# boiler_schematic.net
KiCad netlist of a schematic drawn in EAGLE
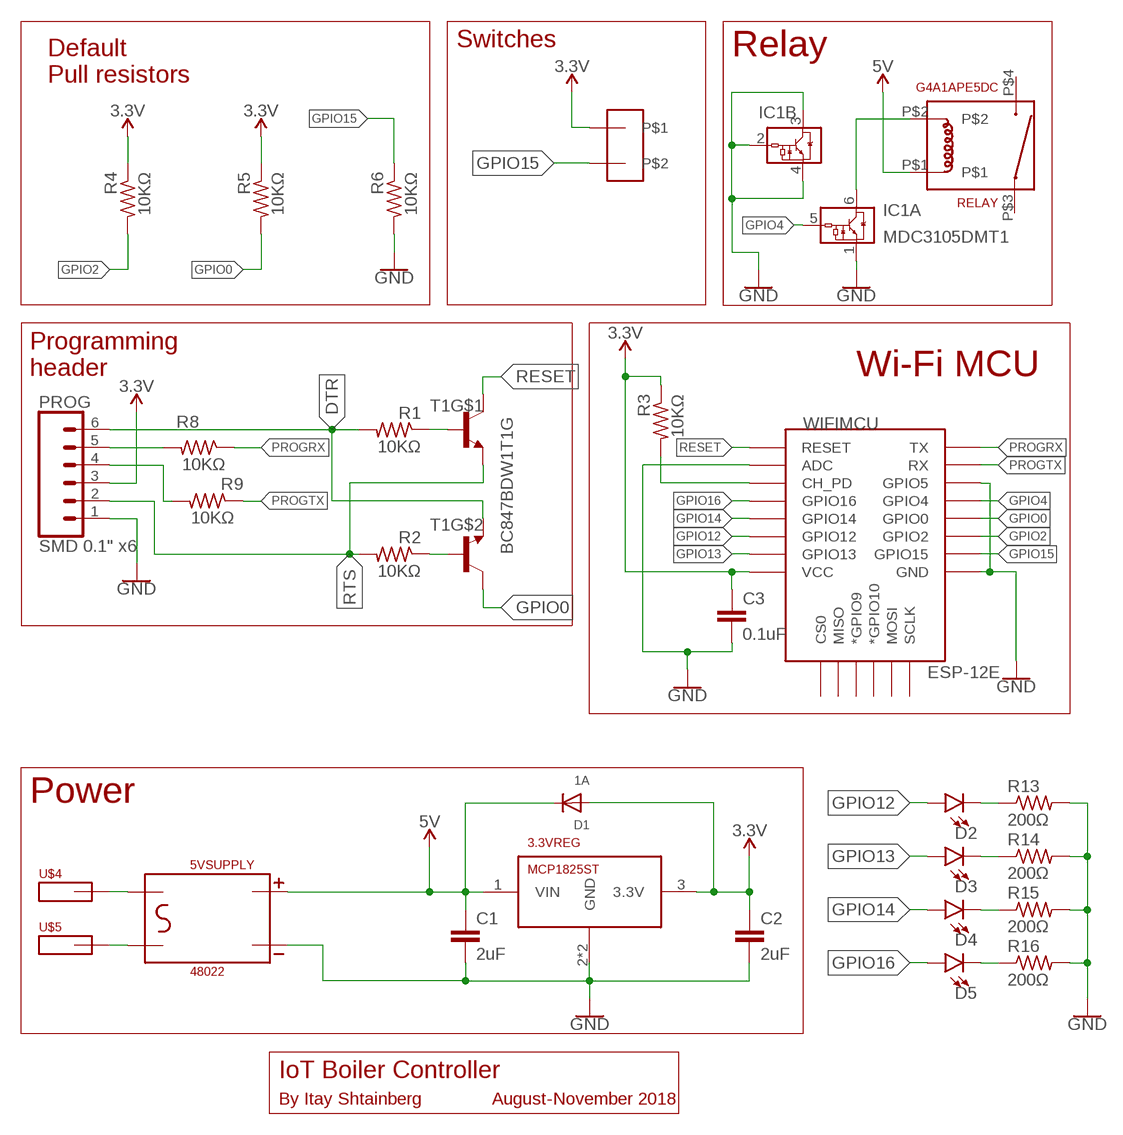
[diagram p0: schematic, sheet 1]

(export (version "E")
  (design (tool "Eeschema 10.0.6"))
  (components
    (comp (ref "3.3VREG")
      (value "MCP1825ST")
      (footprint "eagle-import:SOT223")
      (libsource (lib "eagle-import") (part "MCP1825ST-3302E/DB"))
    )
    (comp (ref "5VSUPPLY")
      (value "48022")
      (footprint "eagle-import:48022")
      (libsource (lib "eagle-import") (part "48022"))
    )
    (comp (ref "C1")
      (value "2uF")
      (footprint "eagle-import:C0805")
      (libsource (lib "eagle-import") (part "C"))
    )
    (comp (ref "C2")
      (value "2uF")
      (footprint "eagle-import:C0805")
      (libsource (lib "eagle-import") (part "C"))
    )
    (comp (ref "C3")
      (value "0.1uF")
      (footprint "eagle-import:C0805")
      (libsource (lib "eagle-import") (part "C"))
    )
    (comp (ref "D1")
      (value "1A")
      (footprint "eagle-import:SOD-123")
      (libsource (lib "eagle-import") (part "DIODESOD-123"))
    )
    (comp (ref "D2")
      (value "LED1206")
      (footprint "eagle-import:LED-1206")
      (libsource (lib "eagle-import") (part "LED1206"))
    )
    (comp (ref "D3")
      (value "LED1206")
      (footprint "eagle-import:LED-1206")
      (libsource (lib "eagle-import") (part "LED1206"))
    )
    (comp (ref "D4")
      (value "LED1206")
      (footprint "eagle-import:LED-1206")
      (libsource (lib "eagle-import") (part "LED1206"))
    )
    (comp (ref "D5")
      (value "LED1206")
      (footprint "eagle-import:LED-1206")
      (libsource (lib "eagle-import") (part "LED1206"))
    )
    (comp (ref "IC1")
      (value "MDC3105DMT1")
      (footprint "eagle-import:SC-74")
      (fields (field (name "MPN") "MDC3105DMT1G"))
      (libsource (lib "eagle-import") (part "MDC3105DMT1"))
    )
    (comp (ref "PROG")
      (value "SMD 0.1\" x6")
      (footprint "eagle-import:1X06-SMD-FEMALE")
      (libsource (lib "eagle-import") (part "CONN_06SMD-FEMALE-V2"))
    )
    (comp (ref "R1")
      (value "10KΩ")
      (footprint "eagle-import:R0805")
      (libsource (lib "eagle-import") (part "rcl_334_R-US_R0805"))
    )
    (comp (ref "R2")
      (value "10KΩ")
      (footprint "eagle-import:R0805")
      (libsource (lib "eagle-import") (part "rcl_334_R-US_R0805"))
    )
    (comp (ref "R3")
      (value "10KΩ")
      (footprint "eagle-import:R0805")
      (libsource (lib "eagle-import") (part "rcl_334_R-US_R0805"))
    )
    (comp (ref "R4")
      (value "10KΩ")
      (footprint "eagle-import:R0805")
      (libsource (lib "eagle-import") (part "rcl_334_R-US_R0805"))
    )
    (comp (ref "R5")
      (value "10KΩ")
      (footprint "eagle-import:R0805")
      (libsource (lib "eagle-import") (part "rcl_334_R-US_R0805"))
    )
    (comp (ref "R6")
      (value "10KΩ")
      (footprint "eagle-import:R0805")
      (libsource (lib "eagle-import") (part "rcl_334_R-US_R0805"))
    )
    (comp (ref "R8")
      (value "10KΩ")
      (footprint "eagle-import:R0805")
      (libsource (lib "eagle-import") (part "rcl_334_R-US_R0805"))
    )
    (comp (ref "R9")
      (value "10KΩ")
      (footprint "eagle-import:R0805")
      (libsource (lib "eagle-import") (part "rcl_334_R-US_R0805"))
    )
    (comp (ref "R13")
      (value "200Ω")
      (footprint "eagle-import:R1206")
      (libsource (lib "eagle-import") (part "R-US_R1206"))
    )
    (comp (ref "R14")
      (value "200Ω")
      (footprint "eagle-import:R1206")
      (libsource (lib "eagle-import") (part "R-US_R1206"))
    )
    (comp (ref "R15")
      (value "200Ω")
      (footprint "eagle-import:R1206")
      (libsource (lib "eagle-import") (part "R-US_R1206"))
    )
    (comp (ref "R16")
      (value "200Ω")
      (footprint "eagle-import:R1206")
      (libsource (lib "eagle-import") (part "R-US_R1206"))
    )
    (comp (ref "RELAY")
      (value "G4A1APE5DC")
      (footprint "eagle-import:G4A-1A-E")
      (libsource (lib "eagle-import") (part "G4A-1A-E"))
    )
    (comp (ref "T1")
      (value "BC847BDW1T1G")
      (footprint "eagle-import:SC70-6")
      (libsource (lib "eagle-import") (part "BC847BDW1T1G"))
    )
    (comp (ref "U$1")
      (value "JST2PIN")
      (footprint "eagle-import:JST2PIN")
      (libsource (lib "eagle-import") (part "JST2PIN"))
    )
    (comp (ref "U$4")
      (value "QUICKDISCONNECT2")
      (footprint "eagle-import:QUICKDISCONNECT2")
      (libsource (lib "eagle-import") (part "QUICKDISCONNECT2"))
    )
    (comp (ref "U$5")
      (value "QUICKDISCONNECT2")
      (footprint "eagle-import:QUICKDISCONNECT2")
      (libsource (lib "eagle-import") (part "QUICKDISCONNECT2"))
    )
    (comp (ref "WIFIMCU")
      (value "ESP-12E")
      (footprint "eagle-import:ESP12E-SMD")
      (libsource (lib "eagle-import") (part "ESP12ESMD"))
    )
  )
  (nets
    (net (code "1") (name "3.3V") (class "Default")
      (node (ref "3.3VREG") (pin "3") (pinfunction "3.3V_3") (pintype "power_in"))
      (node (ref "C2") (pin "1") (pinfunction "1_1") (pintype "passive"))
      (node (ref "C3") (pin "1") (pinfunction "1_1") (pintype "passive"))
      (node (ref "D1") (pin "A") (pinfunction "A_A") (pintype "passive"))
      (node (ref "PROG") (pin "3") (pinfunction "3_3") (pintype "passive"))
      (node (ref "R3") (pin "1") (pinfunction "1_1") (pintype "passive"))
      (node (ref "R4") (pin "1") (pinfunction "1_1") (pintype "passive"))
      (node (ref "R5") (pin "1") (pinfunction "1_1") (pintype "passive"))
      (node (ref "U$1") (pin "P$1") (pinfunction "P$1_P$1") (pintype "bidirectional"))
      (node (ref "WIFIMCU") (pin "VCC") (pinfunction "VCC_VCC") (pintype "bidirectional"))
    )
    (net (code "2") (name "5V") (class "Default")
      (node (ref "3.3VREG") (pin "1") (pinfunction "VIN_1") (pintype "power_in"))
      (node (ref "5VSUPPLY") (pin "+5V") (pinfunction "+5V_+5V") (pintype "bidirectional"))
      (node (ref "C1") (pin "1") (pinfunction "1_1") (pintype "passive"))
      (node (ref "D1") (pin "C") (pinfunction "C_C") (pintype "passive"))
      (node (ref "RELAY") (pin "P$1") (pinfunction "P$1_P$1") (pintype "bidirectional"))
    )
    (net (code "3") (name "DTR") (class "Default")
      (node (ref "PROG") (pin "6") (pinfunction "6_6") (pintype "passive"))
      (node (ref "R1") (pin "2") (pinfunction "2_2") (pintype "passive"))
      (node (ref "T1") (pin "4") (pinfunction "E_4") (pintype "passive"))
    )
    (net (code "4") (name "GND") (class "Default")
      (node (ref "3.3VREG") (pin "2") (pinfunction "GND_2") (pintype "power_in"))
      (node (ref "3.3VREG") (pin "4") (pinfunction "GND_4") (pintype "power_in"))
      (node (ref "5VSUPPLY") (pin "-") (pinfunction "-_-") (pintype "bidirectional"))
      (node (ref "C1") (pin "2") (pinfunction "2_2") (pintype "passive"))
      (node (ref "C2") (pin "2") (pinfunction "2_2") (pintype "passive"))
      (node (ref "C3") (pin "2") (pinfunction "2_2") (pintype "passive"))
      (node (ref "IC1") (pin "1") (pinfunction "GND_1") (pintype "passive"))
      (node (ref "IC1") (pin "2") (pinfunction "VIN_2") (pintype "passive"))
      (node (ref "IC1") (pin "3") (pinfunction "VOUT_3") (pintype "passive"))
      (node (ref "IC1") (pin "4") (pinfunction "GND_4") (pintype "passive"))
      (node (ref "PROG") (pin "1") (pinfunction "1_1") (pintype "passive"))
      (node (ref "R13") (pin "2") (pinfunction "2_2") (pintype "passive"))
      (node (ref "R14") (pin "2") (pinfunction "2_2") (pintype "passive"))
      (node (ref "R15") (pin "2") (pinfunction "2_2") (pintype "passive"))
      (node (ref "R16") (pin "2") (pinfunction "2_2") (pintype "passive"))
      (node (ref "R6") (pin "2") (pinfunction "2_2") (pintype "passive"))
      (node (ref "WIFIMCU") (pin "ADC") (pinfunction "ADC_ADC") (pintype "bidirectional"))
      (node (ref "WIFIMCU") (pin "GND") (pinfunction "GND_GND") (pintype "bidirectional"))
      (node (ref "WIFIMCU") (pin "GPIO5") (pinfunction "GPIO5_GPIO5") (pintype "bidirectional"))
    )
    (net (code "5") (name "GPIO0") (class "Default")
      (node (ref "R5") (pin "2") (pinfunction "2_2") (pintype "passive"))
      (node (ref "T1") (pin "3") (pinfunction "C_3") (pintype "passive"))
      (node (ref "WIFIMCU") (pin "GPIO0") (pinfunction "GPIO0_GPIO0") (pintype "bidirectional"))
    )
    (net (code "6") (name "GPIO2") (class "Default")
      (node (ref "R4") (pin "2") (pinfunction "2_2") (pintype "passive"))
      (node (ref "WIFIMCU") (pin "GPIO2") (pinfunction "GPIO2_GPIO2") (pintype "bidirectional"))
    )
    (net (code "7") (name "GPIO4") (class "Default")
      (node (ref "IC1") (pin "5") (pinfunction "VIN_5") (pintype "passive"))
      (node (ref "WIFIMCU") (pin "GPIO4") (pinfunction "GPIO4_GPIO4") (pintype "bidirectional"))
    )
    (net (code "8") (name "GPIO12") (class "Default")
      (node (ref "D2") (pin "A") (pinfunction "A_A") (pintype "passive"))
      (node (ref "WIFIMCU") (pin "GPIO12") (pinfunction "GPIO12_GPIO12") (pintype "bidirectional"))
    )
    (net (code "9") (name "GPIO13") (class "Default")
      (node (ref "D3") (pin "A") (pinfunction "A_A") (pintype "passive"))
      (node (ref "WIFIMCU") (pin "GPIO13") (pinfunction "GPIO13_GPIO13") (pintype "bidirectional"))
    )
    (net (code "10") (name "GPIO14") (class "Default")
      (node (ref "D4") (pin "A") (pinfunction "A_A") (pintype "passive"))
      (node (ref "WIFIMCU") (pin "GPIO14") (pinfunction "GPIO14_GPIO14") (pintype "bidirectional"))
    )
    (net (code "11") (name "GPIO15") (class "Default")
      (node (ref "R6") (pin "1") (pinfunction "1_1") (pintype "passive"))
      (node (ref "U$1") (pin "P$2") (pinfunction "P$2_P$2") (pintype "bidirectional"))
      (node (ref "WIFIMCU") (pin "GPIO15") (pinfunction "GPIO15_GPIO15") (pintype "bidirectional"))
    )
    (net (code "12") (name "GPIO16") (class "Default")
      (node (ref "D5") (pin "A") (pinfunction "A_A") (pintype "passive"))
      (node (ref "WIFIMCU") (pin "GPIO16") (pinfunction "GPIO16_GPIO16") (pintype "bidirectional"))
    )
    (net (code "13") (name "Net-(5VSUPPLY-PadAC1)") (class "Default")
      (node (ref "5VSUPPLY") (pin "AC1") (pinfunction "AC1_AC1") (pintype "bidirectional"))
      (node (ref "U$4") (pin "P$1") (pinfunction "P$1_P$1") (pintype "bidirectional"))
      (node (ref "U$4") (pin "P$2") (pinfunction "P$1_P$2") (pintype "bidirectional"))
      (node (ref "U$4") (pin "P$3") (pinfunction "P$1_P$3") (pintype "bidirectional"))
      (node (ref "U$4") (pin "P$4") (pinfunction "P$1_P$4") (pintype "bidirectional"))
    )
    (net (code "14") (name "Net-(5VSUPPLY-PadAC2)") (class "Default")
      (node (ref "5VSUPPLY") (pin "AC2") (pinfunction "AC2_AC2") (pintype "bidirectional"))
      (node (ref "U$5") (pin "P$1") (pinfunction "P$1_P$1") (pintype "bidirectional"))
      (node (ref "U$5") (pin "P$2") (pinfunction "P$1_P$2") (pintype "bidirectional"))
      (node (ref "U$5") (pin "P$3") (pinfunction "P$1_P$3") (pintype "bidirectional"))
      (node (ref "U$5") (pin "P$4") (pinfunction "P$1_P$4") (pintype "bidirectional"))
    )
    (net (code "15") (name "Net-(D2-PadC)") (class "Default")
      (node (ref "D2") (pin "C") (pinfunction "C_C") (pintype "passive"))
      (node (ref "R13") (pin "1") (pinfunction "1_1") (pintype "passive"))
    )
    (net (code "16") (name "Net-(D3-PadC)") (class "Default")
      (node (ref "D3") (pin "C") (pinfunction "C_C") (pintype "passive"))
      (node (ref "R14") (pin "1") (pinfunction "1_1") (pintype "passive"))
    )
    (net (code "17") (name "Net-(D4-PadC)") (class "Default")
      (node (ref "D4") (pin "C") (pinfunction "C_C") (pintype "passive"))
      (node (ref "R15") (pin "1") (pinfunction "1_1") (pintype "passive"))
    )
    (net (code "18") (name "Net-(D5-PadC)") (class "Default")
      (node (ref "D5") (pin "C") (pinfunction "C_C") (pintype "passive"))
      (node (ref "R16") (pin "1") (pinfunction "1_1") (pintype "passive"))
    )
    (net (code "19") (name "Net-(IC1A-VOUT)") (class "Default")
      (node (ref "IC1") (pin "6") (pinfunction "VOUT_6") (pintype "passive"))
      (node (ref "RELAY") (pin "P$2") (pinfunction "P$2_P$2") (pintype "bidirectional"))
    )
    (net (code "20") (name "Net-(PROG-Pad4)") (class "Default")
      (node (ref "PROG") (pin "4") (pinfunction "4_4") (pintype "passive"))
      (node (ref "R9") (pin "2") (pinfunction "2_2") (pintype "passive"))
    )
    (net (code "21") (name "Net-(PROG-Pad5)") (class "Default")
      (node (ref "PROG") (pin "5") (pinfunction "5_5") (pintype "passive"))
      (node (ref "R8") (pin "2") (pinfunction "2_2") (pintype "passive"))
    )
    (net (code "22") (name "Net-(R3-Pad2)") (class "Default")
      (node (ref "R3") (pin "2") (pinfunction "2_2") (pintype "passive"))
      (node (ref "WIFIMCU") (pin "CH_PD") (pinfunction "CH_PD_CH_PD") (pintype "bidirectional"))
    )
    (net (code "23") (name "Net-(T1A-B)") (class "Default")
      (node (ref "R1") (pin "1") (pinfunction "1_1") (pintype "passive"))
      (node (ref "T1") (pin "2") (pinfunction "B_2") (pintype "passive"))
    )
    (net (code "24") (name "Net-(T1B-B)") (class "Default")
      (node (ref "R2") (pin "1") (pinfunction "1_1") (pintype "passive"))
      (node (ref "T1") (pin "5") (pinfunction "B_5") (pintype "passive"))
    )
    (net (code "25") (name "PROGRX") (class "Default")
      (node (ref "R8") (pin "1") (pinfunction "1_1") (pintype "passive"))
      (node (ref "WIFIMCU") (pin "TXD0") (pinfunction "TX_TXD0") (pintype "bidirectional"))
    )
    (net (code "26") (name "PROGTX") (class "Default")
      (node (ref "R9") (pin "1") (pinfunction "1_1") (pintype "passive"))
      (node (ref "WIFIMCU") (pin "RXD0") (pinfunction "RX_RXD0") (pintype "bidirectional"))
    )
    (net (code "27") (name "RESET") (class "Default")
      (node (ref "T1") (pin "6") (pinfunction "C_6") (pintype "passive"))
      (node (ref "WIFIMCU") (pin "RESET") (pinfunction "RESET_RESET") (pintype "bidirectional"))
    )
    (net (code "28") (name "RTS") (class "Default")
      (node (ref "PROG") (pin "2") (pinfunction "2_2") (pintype "passive"))
      (node (ref "R2") (pin "2") (pinfunction "2_2") (pintype "passive"))
      (node (ref "T1") (pin "1") (pinfunction "E_1") (pintype "passive"))
    )
    (net (code "29") (name "unconnected-(RELAY-CO-PadP$3)") (class "Default")
      (node (ref "RELAY") (pin "P$3") (pinfunction "CO_P$3") (pintype "bidirectional"))
    )
    (net (code "30") (name "unconnected-(RELAY-NO-PadP$4)") (class "Default")
      (node (ref "RELAY") (pin "P$4") (pinfunction "NO_P$4") (pintype "bidirectional"))
    )
    (net (code "31") (name "unconnected-(WIFIMCU-*GPIO9-PadGPIO9)") (class "Default")
      (node (ref "WIFIMCU") (pin "GPIO9") (pinfunction "*GPIO9_GPIO9") (pintype "bidirectional"))
    )
    (net (code "32") (name "unconnected-(WIFIMCU-*GPIO10-PadGPIO10)") (class "Default")
      (node (ref "WIFIMCU") (pin "GPIO10") (pinfunction "*GPIO10_GPIO10") (pintype "bidirectional"))
    )
    (net (code "33") (name "unconnected-(WIFIMCU-PadCS0)") (class "Default")
      (node (ref "WIFIMCU") (pin "CS0") (pinfunction "CS0_CS0") (pintype "bidirectional"))
    )
    (net (code "34") (name "unconnected-(WIFIMCU-PadMISO)") (class "Default")
      (node (ref "WIFIMCU") (pin "MISO") (pinfunction "MISO_MISO") (pintype "bidirectional"))
    )
    (net (code "35") (name "unconnected-(WIFIMCU-PadMOSI)") (class "Default")
      (node (ref "WIFIMCU") (pin "MOSI") (pinfunction "MOSI_MOSI") (pintype "bidirectional"))
    )
    (net (code "36") (name "unconnected-(WIFIMCU-PadSCLK)") (class "Default")
      (node (ref "WIFIMCU") (pin "SCLK") (pinfunction "SCLK_SCLK") (pintype "bidirectional"))
    )
  )
)
